# ReleaseRev1.net
KiCad netlist of a schematic drawn in EAGLE
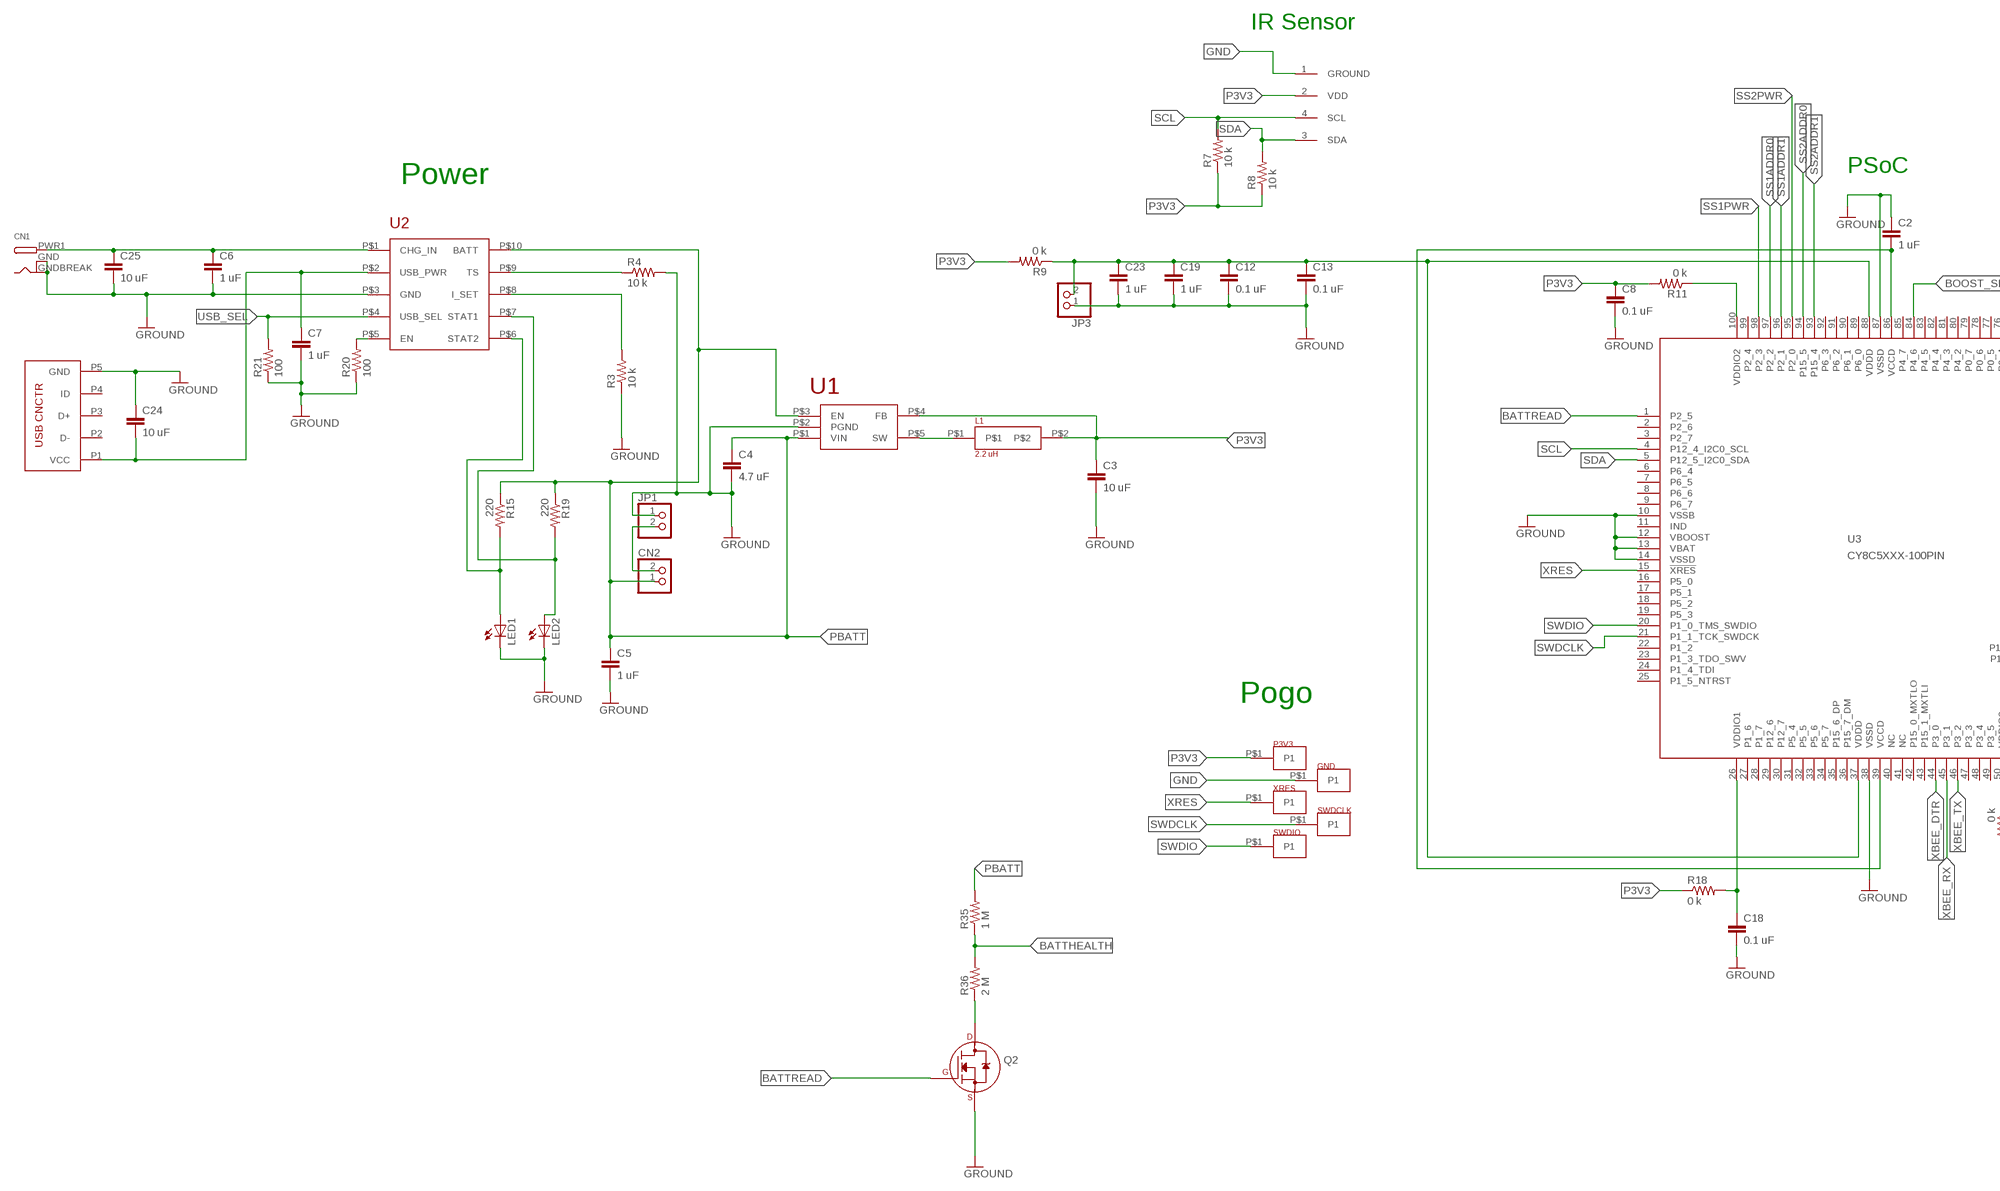
[diagram p0: schematic, sheet 1, part 1 of 2]
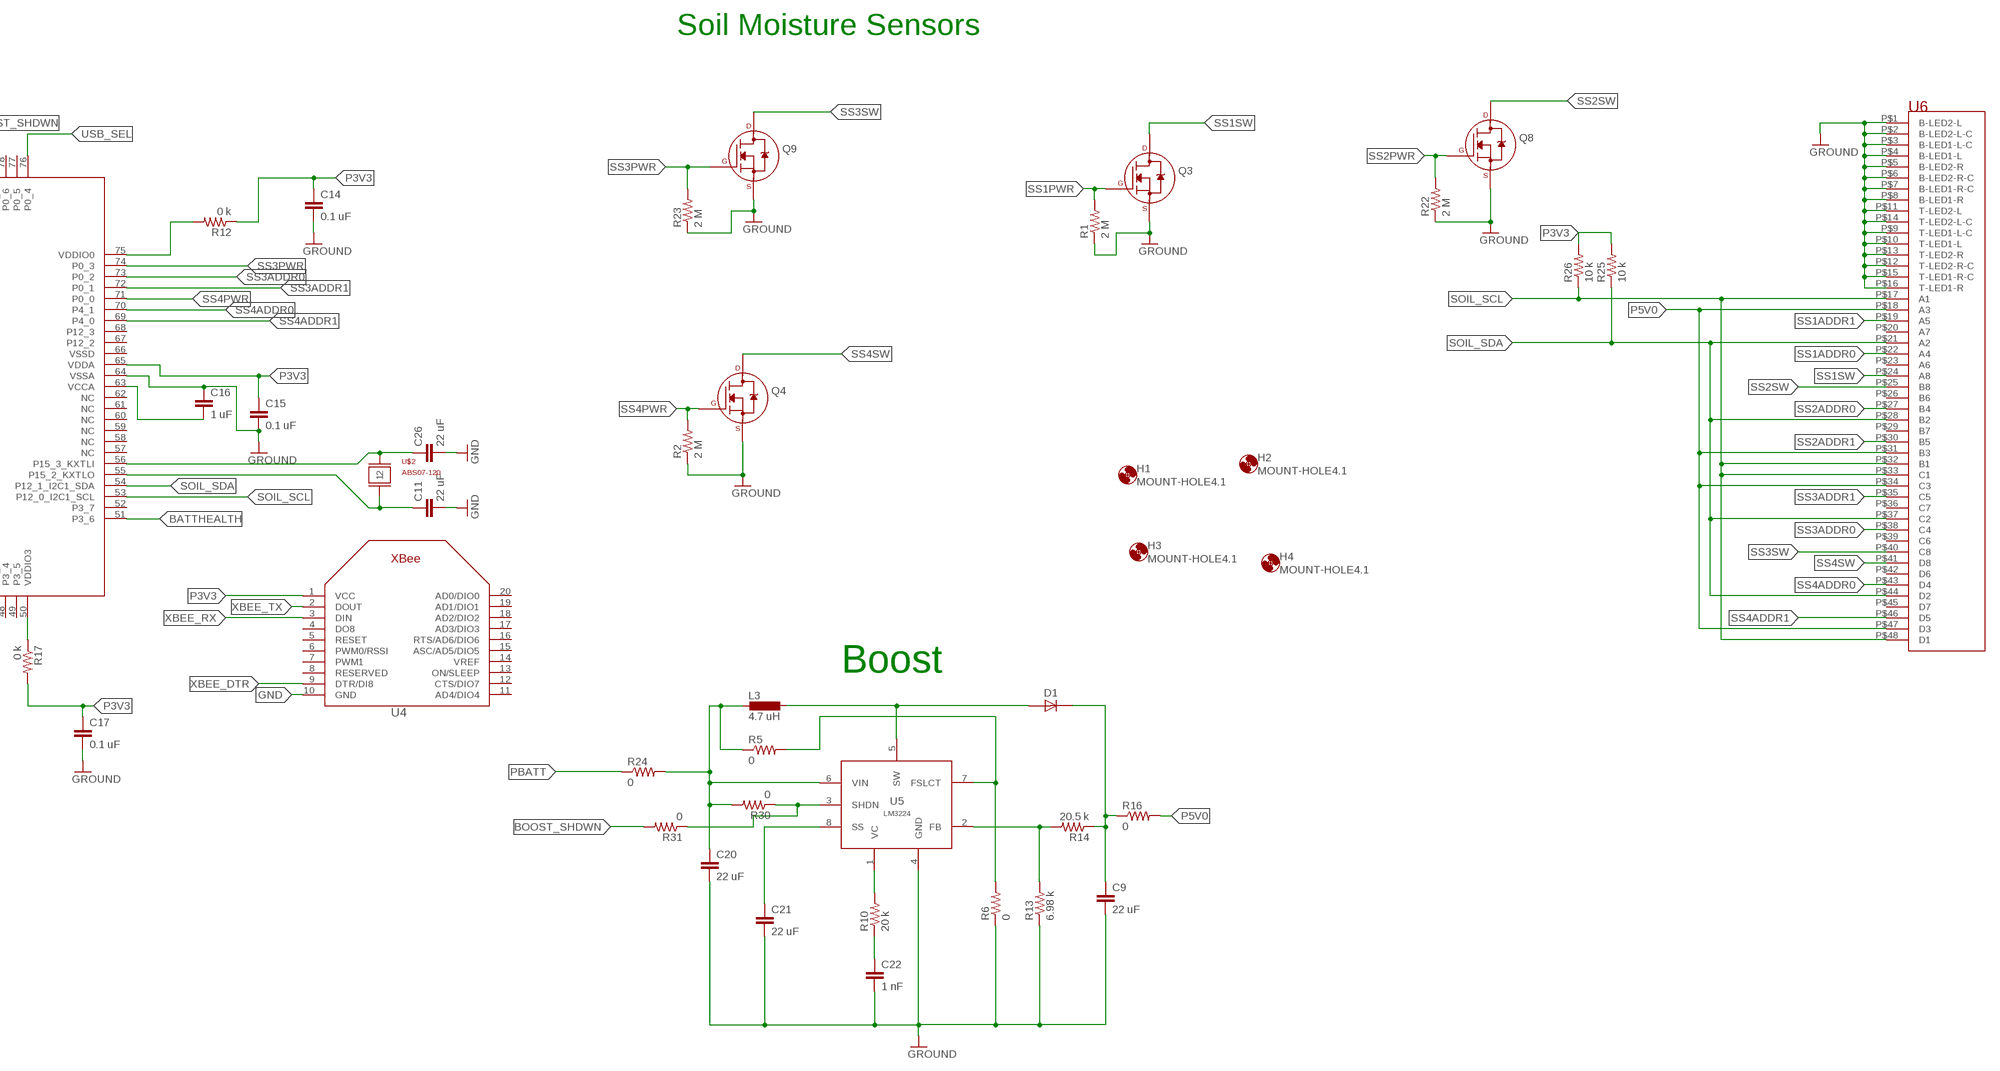
[diagram p1: schematic, sheet 1, part 2 of 2]

(export (version "E")
  (design (tool "Eeschema 10.0.6"))
  (components
    (comp (ref "C2")
      (value "1 uF")
      (footprint "eagle-import:0603")
      (libsource (lib "eagle-import") (part "CAPACITOR0603"))
    )
    (comp (ref "C3")
      (value "10 uF")
      (footprint "eagle-import:0603")
      (libsource (lib "eagle-import") (part "CAPACITOR0603"))
    )
    (comp (ref "C4")
      (value "4.7 uF")
      (footprint "eagle-import:0603")
      (libsource (lib "eagle-import") (part "CAPACITOR0603"))
    )
    (comp (ref "C5")
      (value "1 uF")
      (footprint "eagle-import:0603")
      (libsource (lib "eagle-import") (part "CAPACITOR0603"))
    )
    (comp (ref "C6")
      (value "1 uF")
      (footprint "eagle-import:0603")
      (libsource (lib "eagle-import") (part "CAPACITOR0603"))
    )
    (comp (ref "C7")
      (value "1 uF")
      (footprint "eagle-import:0603")
      (libsource (lib "eagle-import") (part "CAPACITOR0603"))
    )
    (comp (ref "C8")
      (value "0.1 uF")
      (footprint "eagle-import:0603")
      (libsource (lib "eagle-import") (part "CAPACITOR0603"))
    )
    (comp (ref "C9")
      (value "22 uF")
      (footprint "eagle-import:0603")
      (libsource (lib "eagle-import") (part "CAPACITOR0603"))
    )
    (comp (ref "C11")
      (value "22 uF")
      (footprint "eagle-import:0603")
      (libsource (lib "eagle-import") (part "CAPACITOR0603"))
    )
    (comp (ref "C12")
      (value "0.1 uF")
      (footprint "eagle-import:0603")
      (libsource (lib "eagle-import") (part "CAPACITOR0603"))
    )
    (comp (ref "C13")
      (value "0.1 uF")
      (footprint "eagle-import:0603")
      (libsource (lib "eagle-import") (part "CAPACITOR0603"))
    )
    (comp (ref "C14")
      (value "0.1 uF")
      (footprint "eagle-import:0603")
      (libsource (lib "eagle-import") (part "CAPACITOR0603"))
    )
    (comp (ref "C15")
      (value "0.1 uF")
      (footprint "eagle-import:0603")
      (libsource (lib "eagle-import") (part "CAPACITOR0603"))
    )
    (comp (ref "C16")
      (value "1 uF")
      (footprint "eagle-import:0603")
      (libsource (lib "eagle-import") (part "CAPACITOR0603"))
    )
    (comp (ref "C17")
      (value "0.1 uF")
      (footprint "eagle-import:0603")
      (libsource (lib "eagle-import") (part "CAPACITOR0603"))
    )
    (comp (ref "C18")
      (value "0.1 uF")
      (footprint "eagle-import:0603")
      (libsource (lib "eagle-import") (part "CAPACITOR0603"))
    )
    (comp (ref "C19")
      (value "1 uF")
      (footprint "eagle-import:0603")
      (libsource (lib "eagle-import") (part "CAPACITOR0603"))
    )
    (comp (ref "C20")
      (value "22 uF")
      (footprint "eagle-import:0603")
      (libsource (lib "eagle-import") (part "CAPACITOR0603"))
    )
    (comp (ref "C21")
      (value "22 uF")
      (footprint "eagle-import:0603")
      (libsource (lib "eagle-import") (part "CAPACITOR0603"))
    )
    (comp (ref "C22")
      (value "1 nF")
      (footprint "eagle-import:0603")
      (libsource (lib "eagle-import") (part "CAPACITOR0603"))
    )
    (comp (ref "C23")
      (value "1 uF")
      (footprint "eagle-import:0603")
      (libsource (lib "eagle-import") (part "CAPACITOR0603"))
    )
    (comp (ref "C24")
      (value "10 uF")
      (footprint "eagle-import:0603")
      (libsource (lib "eagle-import") (part "CAPACITOR0603"))
    )
    (comp (ref "C25")
      (value "10 uF")
      (footprint "eagle-import:0603")
      (libsource (lib "eagle-import") (part "CAPACITOR0603"))
    )
    (comp (ref "C26")
      (value "22 uF")
      (footprint "eagle-import:0603")
      (libsource (lib "eagle-import") (part "CAPACITOR0603"))
    )
    (comp (ref "CN1")
      (value "DCBARRELSMT")
      (footprint "eagle-import:DCJACK_2MM_SMT")
      (libsource (lib "eagle-import") (part "DCBARRELSMT"))
    )
    (comp (ref "CN2")
      (value "JST_2PIN-SMT-RA")
      (footprint "eagle-import:JST-PH-2-SMT-RA")
      (libsource (lib "eagle-import") (part "JST_2PIN-SMT-RA"))
    )
    (comp (ref "D1")
      (value "DIODE")
      (footprint "eagle-import:0603-LED")
      (libsource (lib "eagle-import") (part "DIODE"))
    )
    (comp (ref "GND")
      (value "POGO-MOUNTING")
      (footprint "eagle-import:POGO-MOUNTING")
      (libsource (lib "eagle-import") (part "POGO-MOUNTING"))
    )
    (comp (ref "H1")
      (value "MOUNT-HOLE4.1")
      (footprint "eagle-import:4,1")
      (libsource (lib "eagle-import") (part "MOUNT-HOLE4.1"))
    )
    (comp (ref "H2")
      (value "MOUNT-HOLE4.1")
      (footprint "eagle-import:4,1")
      (libsource (lib "eagle-import") (part "MOUNT-HOLE4.1"))
    )
    (comp (ref "H3")
      (value "MOUNT-HOLE4.1")
      (footprint "eagle-import:4,1")
      (libsource (lib "eagle-import") (part "MOUNT-HOLE4.1"))
    )
    (comp (ref "H4")
      (value "MOUNT-HOLE4.1")
      (footprint "eagle-import:4,1")
      (libsource (lib "eagle-import") (part "MOUNT-HOLE4.1"))
    )
    (comp (ref "IRSENSOR")
      (value "TO39")
      (footprint "eagle-import:TO39")
      (libsource (lib "eagle-import") (part "TO39"))
    )
    (comp (ref "JP1")
      (value "PINHD-1X2")
      (footprint "eagle-import:1X02")
      (libsource (lib "eagle-import") (part "PINHD-1X2"))
    )
    (comp (ref "JP3")
      (value "PINHD-1X2")
      (footprint "eagle-import:1X02")
      (libsource (lib "eagle-import") (part "PINHD-1X2"))
    )
    (comp (ref "L1")
      (value "LPO3310")
      (footprint "eagle-import:LPO3310")
      (libsource (lib "eagle-import") (part "LPO3310"))
    )
    (comp (ref "L3")
      (value "4.7 uH")
      (footprint "eagle-import:DO3316P")
      (libsource (lib "eagle-import") (part "DO3316P"))
    )
    (comp (ref "LED1")
      (value "LEDCHIP-LED0603")
      (footprint "eagle-import:CHIP-LED0603")
      (libsource (lib "eagle-import") (part "LEDCHIP-LED0603"))
    )
    (comp (ref "LED2")
      (value "LEDCHIP-LED0603")
      (footprint "eagle-import:CHIP-LED0603")
      (libsource (lib "eagle-import") (part "LEDCHIP-LED0603"))
    )
    (comp (ref "P3V3")
      (value "POGO-MOUNTING")
      (footprint "eagle-import:POGO-MOUNTING")
      (libsource (lib "eagle-import") (part "POGO-MOUNTING"))
    )
    (comp (ref "Q2")
      (value "2N7000_SOT23")
      (footprint "eagle-import:SOT-23")
      (libsource (lib "eagle-import") (part "2N700_SOT230"))
    )
    (comp (ref "Q3")
      (value "2N7000_SOT23")
      (footprint "eagle-import:SOT-23")
      (libsource (lib "eagle-import") (part "2N700_SOT230"))
    )
    (comp (ref "Q4")
      (value "2N7000_SOT23")
      (footprint "eagle-import:SOT-23")
      (libsource (lib "eagle-import") (part "2N700_SOT230"))
    )
    (comp (ref "Q8")
      (value "2N7000_SOT23")
      (footprint "eagle-import:SOT-23")
      (libsource (lib "eagle-import") (part "2N700_SOT230"))
    )
    (comp (ref "Q9")
      (value "2N7000_SOT23")
      (footprint "eagle-import:SOT-23")
      (libsource (lib "eagle-import") (part "2N700_SOT230"))
    )
    (comp (ref "R1")
      (value "2 M")
      (footprint "eagle-import:0603")
      (libsource (lib "eagle-import") (part "RESISTOR0603"))
    )
    (comp (ref "R2")
      (value "2 M")
      (footprint "eagle-import:0603")
      (libsource (lib "eagle-import") (part "RESISTOR0603"))
    )
    (comp (ref "R3")
      (value "10 k")
      (footprint "eagle-import:0603")
      (libsource (lib "eagle-import") (part "RESISTOR0603"))
    )
    (comp (ref "R4")
      (value "10 k")
      (footprint "eagle-import:0603")
      (libsource (lib "eagle-import") (part "RESISTOR0603"))
    )
    (comp (ref "R5")
      (value "0")
      (footprint "eagle-import:0603")
      (libsource (lib "eagle-import") (part "RESISTOR0603"))
    )
    (comp (ref "R6")
      (value "0")
      (footprint "eagle-import:0603")
      (libsource (lib "eagle-import") (part "RESISTOR0603"))
    )
    (comp (ref "R7")
      (value "10 k")
      (footprint "eagle-import:0603")
      (libsource (lib "eagle-import") (part "RESISTOR0603"))
    )
    (comp (ref "R8")
      (value "10 k")
      (footprint "eagle-import:0603")
      (libsource (lib "eagle-import") (part "RESISTOR0603"))
    )
    (comp (ref "R9")
      (value "0 k")
      (footprint "eagle-import:0603")
      (libsource (lib "eagle-import") (part "RESISTOR0603"))
    )
    (comp (ref "R10")
      (value "20 k")
      (footprint "eagle-import:0603")
      (libsource (lib "eagle-import") (part "RESISTOR0603"))
    )
    (comp (ref "R11")
      (value "0 k")
      (footprint "eagle-import:0603")
      (libsource (lib "eagle-import") (part "RESISTOR0603"))
    )
    (comp (ref "R12")
      (value "0 k")
      (footprint "eagle-import:0603")
      (libsource (lib "eagle-import") (part "RESISTOR0603"))
    )
    (comp (ref "R13")
      (value "6.98 k")
      (footprint "eagle-import:0603")
      (libsource (lib "eagle-import") (part "RESISTOR0603"))
    )
    (comp (ref "R14")
      (value "20.5 k")
      (footprint "eagle-import:0603")
      (libsource (lib "eagle-import") (part "RESISTOR0603"))
    )
    (comp (ref "R15")
      (value "220")
      (footprint "eagle-import:0603")
      (libsource (lib "eagle-import") (part "RESISTOR0603"))
    )
    (comp (ref "R16")
      (value "0")
      (footprint "eagle-import:R2010")
      (libsource (lib "eagle-import") (part "R-US_R2010"))
    )
    (comp (ref "R17")
      (value "0 k")
      (footprint "eagle-import:0603")
      (libsource (lib "eagle-import") (part "RESISTOR0603"))
    )
    (comp (ref "R18")
      (value "0 k")
      (footprint "eagle-import:0603")
      (libsource (lib "eagle-import") (part "RESISTOR0603"))
    )
    (comp (ref "R19")
      (value "220")
      (footprint "eagle-import:0603")
      (libsource (lib "eagle-import") (part "RESISTOR0603"))
    )
    (comp (ref "R20")
      (value "100")
      (footprint "eagle-import:0603")
      (libsource (lib "eagle-import") (part "RESISTOR0603"))
    )
    (comp (ref "R21")
      (value "100")
      (footprint "eagle-import:0603")
      (libsource (lib "eagle-import") (part "RESISTOR0603"))
    )
    (comp (ref "R22")
      (value "2 M")
      (footprint "eagle-import:0603")
      (libsource (lib "eagle-import") (part "RESISTOR0603"))
    )
    (comp (ref "R23")
      (value "2 M")
      (footprint "eagle-import:0603")
      (libsource (lib "eagle-import") (part "RESISTOR0603"))
    )
    (comp (ref "R24")
      (value "0")
      (footprint "eagle-import:R2010")
      (libsource (lib "eagle-import") (part "R-US_R2010"))
    )
    (comp (ref "R25")
      (value "10 k")
      (footprint "eagle-import:0603")
      (libsource (lib "eagle-import") (part "RESISTOR0603"))
    )
    (comp (ref "R26")
      (value "10 k")
      (footprint "eagle-import:0603")
      (libsource (lib "eagle-import") (part "RESISTOR0603"))
    )
    (comp (ref "R30")
      (value "0")
      (footprint "eagle-import:0603")
      (libsource (lib "eagle-import") (part "RESISTOR0603"))
    )
    (comp (ref "R31")
      (value "0")
      (footprint "eagle-import:0603")
      (libsource (lib "eagle-import") (part "RESISTOR0603"))
    )
    (comp (ref "R35")
      (value "1 M")
      (footprint "eagle-import:0603")
      (libsource (lib "eagle-import") (part "RESISTOR0603"))
    )
    (comp (ref "R36")
      (value "2 M")
      (footprint "eagle-import:0603")
      (libsource (lib "eagle-import") (part "RESISTOR0603"))
    )
    (comp (ref "SWDCLK")
      (value "POGO-MOUNTING")
      (footprint "eagle-import:POGO-MOUNTING")
      (libsource (lib "eagle-import") (part "POGO-MOUNTING"))
    )
    (comp (ref "SWDIO")
      (value "POGO-MOUNTING")
      (footprint "eagle-import:POGO-MOUNTING")
      (libsource (lib "eagle-import") (part "POGO-MOUNTING"))
    )
    (comp (ref "U$1")
      (value "FCI10118192-0001LF")
      (footprint "eagle-import:FCI10118192-0001LF")
      (libsource (lib "eagle-import") (part "FCI10118192-0001LF"))
    )
    (comp (ref "U$2")
      (value "ABS07-120")
      (footprint "eagle-import:2-SMD")
      (libsource (lib "eagle-import") (part "ABS07-120"))
    )
    (comp (ref "U1")
      (value "LM3671-407564")
      (footprint "eagle-import:LM3671-407564")
      (libsource (lib "eagle-import") (part "LM3671-407564"))
    )
    (comp (ref "U2")
      (value "LM3658")
      (footprint "eagle-import:LM3658")
      (libsource (lib "eagle-import") (part "LM3658"))
    )
    (comp (ref "U3")
      (value "CY8C5XXX-100PIN")
      (footprint "eagle-import:TQFP-14X14-100")
      (fields (field (name "MPN") "CY8C5588AXI-060"))
      (libsource (lib "eagle-import") (part "CY8C5XXX-100PIN"))
    )
    (comp (ref "U4")
      (value "XBEE")
      (footprint "eagle-import:XBEE")
      (libsource (lib "eagle-import") (part "XBEE"))
    )
    (comp (ref "U5")
      (value "LM3224")
      (footprint "eagle-import:MSOP-8")
      (libsource (lib "eagle-import") (part "LM3224"))
    )
    (comp (ref "U6")
      (value "RJSAE-5380-04")
      (footprint "eagle-import:RJSAE-5380-04")
      (libsource (lib "eagle-import") (part "RJSAE-5380-04"))
    )
    (comp (ref "XRES")
      (value "POGO-MOUNTING")
      (footprint "eagle-import:POGO-MOUNTING")
      (libsource (lib "eagle-import") (part "POGO-MOUNTING"))
    )
  )
  (nets
    (net (code "1") (name "BATTHEALTH") (class "Default")
      (node (ref "R35") (pin "1") (pinfunction "1_1") (pintype "passive"))
      (node (ref "R36") (pin "2") (pinfunction "2_2") (pintype "passive"))
      (node (ref "U3") (pin "51") (pinfunction "P3_6_51") (pintype "passive"))
    )
    (net (code "2") (name "BATTREAD") (class "Default")
      (node (ref "Q2") (pin "1") (pinfunction "G_1") (pintype "tri_state"))
      (node (ref "U3") (pin "1") (pinfunction "P2_5_1") (pintype "passive"))
    )
    (net (code "3") (name "BOOST_SHDWN") (class "Default")
      (node (ref "R31") (pin "2") (pinfunction "2_2") (pintype "passive"))
      (node (ref "U3") (pin "84") (pinfunction "P4_6_84") (pintype "passive"))
    )
    (net (code "4") (name "GND") (class "Default")
      (node (ref "C11") (pin "2") (pinfunction "2_2") (pintype "passive"))
      (node (ref "C12") (pin "2") (pinfunction "2_2") (pintype "passive"))
      (node (ref "C13") (pin "2") (pinfunction "2_2") (pintype "passive"))
      (node (ref "C14") (pin "2") (pinfunction "2_2") (pintype "passive"))
      (node (ref "C15") (pin "2") (pinfunction "2_2") (pintype "passive"))
      (node (ref "C16") (pin "1") (pinfunction "1_1") (pintype "passive"))
      (node (ref "C17") (pin "2") (pinfunction "2_2") (pintype "passive"))
      (node (ref "C18") (pin "2") (pinfunction "2_2") (pintype "passive"))
      (node (ref "C19") (pin "2") (pinfunction "2_2") (pintype "passive"))
      (node (ref "C2") (pin "1") (pinfunction "1_1") (pintype "passive"))
      (node (ref "C20") (pin "2") (pinfunction "2_2") (pintype "passive"))
      (node (ref "C21") (pin "2") (pinfunction "2_2") (pintype "passive"))
      (node (ref "C22") (pin "2") (pinfunction "2_2") (pintype "passive"))
      (node (ref "C23") (pin "2") (pinfunction "2_2") (pintype "passive"))
      (node (ref "C24") (pin "1") (pinfunction "1_1") (pintype "passive"))
      (node (ref "C25") (pin "2") (pinfunction "2_2") (pintype "passive"))
      (node (ref "C26") (pin "2") (pinfunction "2_2") (pintype "passive"))
      (node (ref "C3") (pin "2") (pinfunction "2_2") (pintype "passive"))
      (node (ref "C4") (pin "2") (pinfunction "2_2") (pintype "passive"))
      (node (ref "C5") (pin "2") (pinfunction "2_2") (pintype "passive"))
      (node (ref "C6") (pin "2") (pinfunction "2_2") (pintype "passive"))
      (node (ref "C7") (pin "2") (pinfunction "2_2") (pintype "passive"))
      (node (ref "C8") (pin "2") (pinfunction "2_2") (pintype "passive"))
      (node (ref "C9") (pin "2") (pinfunction "2_2") (pintype "passive"))
      (node (ref "CN1") (pin "GND") (pinfunction "GNDBREAK_GND") (pintype "power_in"))
      (node (ref "CN1") (pin "GNDBREAK") (pinfunction "GND_GNDBREAK") (pintype "power_in"))
      (node (ref "GND") (pin "P$1") (pinfunction "P1_P$1") (pintype "bidirectional"))
      (node (ref "IRSENSOR") (pin "1") (pinfunction "GROUND_1") (pintype "bidirectional"))
      (node (ref "JP1") (pin "1") (pinfunction "1_1") (pintype "passive"))
      (node (ref "JP3") (pin "1") (pinfunction "1_1") (pintype "passive"))
      (node (ref "LED1") (pin "C") (pinfunction "C_C") (pintype "passive"))
      (node (ref "LED2") (pin "C") (pinfunction "C_C") (pintype "passive"))
      (node (ref "Q2") (pin "2") (pinfunction "S_2") (pintype "bidirectional"))
      (node (ref "Q3") (pin "2") (pinfunction "S_2") (pintype "bidirectional"))
      (node (ref "Q4") (pin "2") (pinfunction "S_2") (pintype "bidirectional"))
      (node (ref "Q8") (pin "2") (pinfunction "S_2") (pintype "bidirectional"))
      (node (ref "Q9") (pin "2") (pinfunction "S_2") (pintype "bidirectional"))
      (node (ref "R1") (pin "1") (pinfunction "1_1") (pintype "passive"))
      (node (ref "R13") (pin "1") (pinfunction "1_1") (pintype "passive"))
      (node (ref "R2") (pin "1") (pinfunction "1_1") (pintype "passive"))
      (node (ref "R20") (pin "1") (pinfunction "1_1") (pintype "passive"))
      (node (ref "R21") (pin "1") (pinfunction "1_1") (pintype "passive"))
      (node (ref "R22") (pin "1") (pinfunction "1_1") (pintype "passive"))
      (node (ref "R23") (pin "1") (pinfunction "1_1") (pintype "passive"))
      (node (ref "R3") (pin "1") (pinfunction "1_1") (pintype "passive"))
      (node (ref "R4") (pin "2") (pinfunction "2_2") (pintype "passive"))
      (node (ref "R6") (pin "1") (pinfunction "1_1") (pintype "passive"))
      (node (ref "U$1") (pin "P5") (pinfunction "GND_P5") (pintype "power_in"))
      (node (ref "U1") (pin "P$2") (pinfunction "PGND_P$2") (pintype "passive"))
      (node (ref "U2") (pin "P$3") (pinfunction "GND_P$3") (pintype "power_in"))
      (node (ref "U3") (pin "10") (pinfunction "VSSB_10") (pintype "passive"))
      (node (ref "U3") (pin "12") (pinfunction "VBOOST_12") (pintype "passive"))
      (node (ref "U3") (pin "13") (pinfunction "VBAT_13") (pintype "passive"))
      (node (ref "U3") (pin "14") (pinfunction "VSSD_14") (pintype "passive"))
      (node (ref "U3") (pin "38") (pinfunction "VSSD_38") (pintype "passive"))
      (node (ref "U3") (pin "64") (pinfunction "VSSA_64") (pintype "passive"))
      (node (ref "U3") (pin "87") (pinfunction "VSSD_87") (pintype "passive"))
      (node (ref "U4") (pin "10") (pinfunction "GND_10") (pintype "power_in"))
      (node (ref "U5") (pin "4") (pinfunction "GND_4") (pintype "bidirectional"))
      (node (ref "U6") (pin "P$1") (pinfunction "B-LED2-L_P$1") (pintype "bidirectional"))
      (node (ref "U6") (pin "P$10") (pinfunction "T-LED1-L_P$10") (pintype "bidirectional"))
      (node (ref "U6") (pin "P$11") (pinfunction "T-LED2-L_P$11") (pintype "bidirectional"))
      (node (ref "U6") (pin "P$12") (pinfunction "T-LED2-R-C_P$12") (pintype "bidirectional"))
      (node (ref "U6") (pin "P$13") (pinfunction "T-LED2-R_P$13") (pintype "bidirectional"))
      (node (ref "U6") (pin "P$14") (pinfunction "T-LED2-L-C_P$14") (pintype "bidirectional"))
      (node (ref "U6") (pin "P$15") (pinfunction "T-LED1-R-C_P$15") (pintype "bidirectional"))
      (node (ref "U6") (pin "P$16") (pinfunction "T-LED1-R_P$16") (pintype "bidirectional"))
      (node (ref "U6") (pin "P$2") (pinfunction "B-LED2-L-C_P$2") (pintype "bidirectional"))
      (node (ref "U6") (pin "P$3") (pinfunction "B-LED1-L-C_P$3") (pintype "bidirectional"))
      (node (ref "U6") (pin "P$4") (pinfunction "B-LED1-L_P$4") (pintype "bidirectional"))
      (node (ref "U6") (pin "P$5") (pinfunction "B-LED2-R_P$5") (pintype "bidirectional"))
      (node (ref "U6") (pin "P$6") (pinfunction "B-LED2-R-C_P$6") (pintype "bidirectional"))
      (node (ref "U6") (pin "P$7") (pinfunction "B-LED1-R-C_P$7") (pintype "bidirectional"))
      (node (ref "U6") (pin "P$8") (pinfunction "B-LED1-R_P$8") (pintype "bidirectional"))
      (node (ref "U6") (pin "P$9") (pinfunction "T-LED1-L-C_P$9") (pintype "bidirectional"))
    )
    (net (code "5") (name "Net-(C2-Pad2)") (class "Default")
      (node (ref "C2") (pin "2") (pinfunction "2_2") (pintype "passive"))
      (node (ref "U3") (pin "39") (pinfunction "VCCD_39") (pintype "passive"))
      (node (ref "U3") (pin "86") (pinfunction "VCCD_86") (pintype "passive"))
    )
    (net (code "6") (name "Net-(C9-Pad1)") (class "Default")
      (node (ref "C9") (pin "1") (pinfunction "1_1") (pintype "passive"))
      (node (ref "D1") (pin "C") (pinfunction "C_C") (pintype "passive"))
      (node (ref "R14") (pin "1") (pinfunction "1_1") (pintype "passive"))
      (node (ref "R16") (pin "1") (pinfunction "1_1") (pintype "passive"))
    )
    (net (code "7") (name "Net-(C12-Pad1)") (class "Default")
      (node (ref "C12") (pin "1") (pinfunction "1_1") (pintype "passive"))
      (node (ref "C13") (pin "1") (pinfunction "1_1") (pintype "passive"))
      (node (ref "C19") (pin "1") (pinfunction "1_1") (pintype "passive"))
      (node (ref "C23") (pin "1") (pinfunction "1_1") (pintype "passive"))
      (node (ref "JP3") (pin "2") (pinfunction "2_2") (pintype "passive"))
      (node (ref "R9") (pin "1") (pinfunction "1_1") (pintype "passive"))
      (node (ref "U3") (pin "37") (pinfunction "VDDD_37") (pintype "passive"))
      (node (ref "U3") (pin "88") (pinfunction "VDDD_88") (pintype "passive"))
    )
    (net (code "8") (name "Net-(C22-Pad1)") (class "Default")
      (node (ref "C22") (pin "1") (pinfunction "1_1") (pintype "passive"))
      (node (ref "R10") (pin "1") (pinfunction "1_1") (pintype "passive"))
    )
    (net (code "9") (name "Net-(CN1-PWR)") (class "Default")
      (node (ref "C25") (pin "1") (pinfunction "1_1") (pintype "passive"))
      (node (ref "C6") (pin "1") (pinfunction "1_1") (pintype "passive"))
      (node (ref "CN1") (pin "PWR1") (pinfunction "PWR_PWR1") (pintype "power_in"))
      (node (ref "U2") (pin "P$1") (pinfunction "CHG_IN_P$1") (pintype "power_in"))
    )
    (net (code "10") (name "Net-(CN2-1)") (class "Default")
      (node (ref "CN2") (pin "2") (pinfunction "1_2") (pintype "passive"))
      (node (ref "JP1") (pin "2") (pinfunction "2_2") (pintype "passive"))
    )
    (net (code "11") (name "Net-(Q2-D)") (class "Default")
      (node (ref "Q2") (pin "3") (pinfunction "D_3") (pintype "bidirectional"))
      (node (ref "R36") (pin "1") (pinfunction "1_1") (pintype "passive"))
    )
    (net (code "12") (name "Net-(U$1-VCC)") (class "Default")
      (node (ref "C24") (pin "2") (pinfunction "2_2") (pintype "passive"))
      (node (ref "C7") (pin "1") (pinfunction "1_1") (pintype "passive"))
      (node (ref "U$1") (pin "P1") (pinfunction "VCC_P1") (pintype "power_in"))
      (node (ref "U2") (pin "P$2") (pinfunction "USB_PWR_P$2") (pintype "power_in"))
    )
    (net (code "13") (name "Net-(U1-SW)") (class "Default")
      (node (ref "L1") (pin "P$1") (pinfunction "P$1_P$1") (pintype "passive"))
      (node (ref "U1") (pin "P$5") (pinfunction "SW_P$5") (pintype "bidirectional"))
    )
    (net (code "14") (name "Net-(U2-EN)") (class "Default")
      (node (ref "R20") (pin "2") (pinfunction "2_2") (pintype "passive"))
      (node (ref "U2") (pin "P$5") (pinfunction "EN_P$5") (pintype "input"))
    )
    (net (code "15") (name "Net-(U2-I_SET)") (class "Default")
      (node (ref "R3") (pin "2") (pinfunction "2_2") (pintype "passive"))
      (node (ref "U2") (pin "P$8") (pinfunction "I_SET_P$8") (pintype "bidirectional"))
    )
    (net (code "16") (name "Net-(U2-STAT1)") (class "Default")
      (node (ref "LED2") (pin "A") (pinfunction "A_A") (pintype "passive"))
      (node (ref "R19") (pin "2") (pinfunction "2_2") (pintype "passive"))
      (node (ref "U2") (pin "P$7") (pinfunction "STAT1_P$7") (pintype "output"))
    )
    (net (code "17") (name "Net-(U2-STAT2)") (class "Default")
      (node (ref "LED1") (pin "A") (pinfunction "A_A") (pintype "passive"))
      (node (ref "R15") (pin "2") (pinfunction "2_2") (pintype "passive"))
      (node (ref "U2") (pin "P$6") (pinfunction "STAT2_P$6") (pintype "output"))
    )
    (net (code "18") (name "Net-(U2-TS)") (class "Default")
      (node (ref "R4") (pin "1") (pinfunction "1_1") (pintype "passive"))
      (node (ref "U2") (pin "P$9") (pinfunction "TS_P$9") (pintype "bidirectional"))
    )
    (net (code "19") (name "Net-(U3-P15_2_KXTLO)") (class "Default")
      (node (ref "C11") (pin "1") (pinfunction "1_1") (pintype "passive"))
      (node (ref "U$2") (pin "2") (pinfunction "2_2") (pintype "bidirectional"))
      (node (ref "U3") (pin "55") (pinfunction "P15_2_KXTLO_55") (pintype "passive"))
    )
    (net (code "20") (name "Net-(U3-P15_3_KXTLI)") (class "Default")
      (node (ref "C26") (pin "1") (pinfunction "1_1") (pintype "passive"))
      (node (ref "U$2") (pin "1") (pinfunction "1_1") (pintype "bidirectional"))
      (node (ref "U3") (pin "56") (pinfunction "P15_3_KXTLI_56") (pintype "passive"))
    )
    (net (code "21") (name "Net-(U3-VCCA)") (class "Default")
      (node (ref "C16") (pin "2") (pinfunction "2_2") (pintype "passive"))
      (node (ref "U3") (pin "63") (pinfunction "VCCA_63") (pintype "passive"))
    )
    (net (code "22") (name "Net-(U3-VDDIO0)") (class "Default")
      (node (ref "R12") (pin "2") (pinfunction "2_2") (pintype "passive"))
      (node (ref "U3") (pin "75") (pinfunction "VDDIO0_75") (pintype "passive"))
    )
    (net (code "23") (name "Net-(U3-VDDIO1)") (class "Default")
      (node (ref "C18") (pin "1") (pinfunction "1_1") (pintype "passive"))
      (node (ref "R18") (pin "2") (pinfunction "2_2") (pintype "passive"))
      (node (ref "U3") (pin "26") (pinfunction "VDDIO1_26") (pintype "passive"))
    )
    (net (code "24") (name "Net-(U3-VDDIO2)") (class "Default")
      (node (ref "R11") (pin "1") (pinfunction "1_1") (pintype "passive"))
      (node (ref "U3") (pin "100") (pinfunction "VDDIO2_100") (pintype "passive"))
    )
    (net (code "25") (name "Net-(U3-VDDIO3)") (class "Default")
      (node (ref "R17") (pin "1") (pinfunction "1_1") (pintype "passive"))
      (node (ref "U3") (pin "50") (pinfunction "VDDIO3_50") (pintype "passive"))
    )
    (net (code "26") (name "Net-(U5-FB)") (class "Default")
      (node (ref "R13") (pin "2") (pinfunction "2_2") (pintype "passive"))
      (node (ref "R14") (pin "2") (pinfunction "2_2") (pintype "passive"))
      (node (ref "U5") (pin "2") (pinfunction "FB_2") (pintype "bidirectional"))
    )
    (net (code "27") (name "Net-(U5-FSLCT)") (class "Default")
      (node (ref "R5") (pin "2") (pinfunction "2_2") (pintype "passive"))
      (node (ref "R6") (pin "2") (pinfunction "2_2") (pintype "passive"))
      (node (ref "U5") (pin "7") (pinfunction "FSLCT_7") (pintype "bidirectional"))
    )
    (net (code "28") (name "Net-(U5-SHDN)") (class "Default")
      (node (ref "R30") (pin "1") (pinfunction "1_1") (pintype "passive"))
      (node (ref "R31") (pin "1") (pinfunction "1_1") (pintype "passive"))
      (node (ref "U5") (pin "3") (pinfunction "SHDN_3") (pintype "bidirectional"))
    )
    (net (code "29") (name "Net-(U5-SS)") (class "Default")
      (node (ref "C21") (pin "1") (pinfunction "1_1") (pintype "passive"))
      (node (ref "U5") (pin "8") (pinfunction "SS_8") (pintype "bidirectional"))
    )
    (net (code "30") (name "Net-(U5-SW)") (class "Default")
      (node (ref "D1") (pin "A") (pinfunction "A_A") (pintype "passive"))
      (node (ref "L3") (pin "2") (pinfunction "2_2") (pintype "passive"))
      (node (ref "U5") (pin "5") (pinfunction "SW_5") (pintype "bidirectional"))
    )
    (net (code "31") (name "Net-(U5-VC)") (class "Default")
      (node (ref "R10") (pin "2") (pinfunction "2_2") (pintype "passive"))
      (node (ref "U5") (pin "1") (pinfunction "VC_1") (pintype "bidirectional"))
    )
    (net (code "32") (name "Net-(U5-VIN)") (class "Default")
      (node (ref "C20") (pin "1") (pinfunction "1_1") (pintype "passive"))
      (node (ref "L3") (pin "1") (pinfunction "1_1") (pintype "passive"))
      (node (ref "R24") (pin "2") (pinfunction "2_2") (pintype "passive"))
      (node (ref "R30") (pin "2") (pinfunction "2_2") (pintype "passive"))
      (node (ref "R5") (pin "1") (pinfunction "1_1") (pintype "passive"))
      (node (ref "U5") (pin "6") (pinfunction "VIN_6") (pintype "bidirectional"))
    )
    (net (code "33") (name "P3V3") (class "Default")
      (node (ref "C14") (pin "1") (pinfunction "1_1") (pintype "passive"))
      (node (ref "C15") (pin "1") (pinfunction "1_1") (pintype "passive"))
      (node (ref "C17") (pin "1") (pinfunction "1_1") (pintype "passive"))
      (node (ref "C3") (pin "1") (pinfunction "1_1") (pintype "passive"))
      (node (ref "C8") (pin "1") (pinfunction "1_1") (pintype "passive"))
      (node (ref "IRSENSOR") (pin "2") (pinfunction "VDD_2") (pintype "bidirectional"))
      (node (ref "L1") (pin "P$2") (pinfunction "P$2_P$2") (pintype "tri_state"))
      (node (ref "P3V3") (pin "P$1") (pinfunction "P1_P$1") (pintype "bidirectional"))
      (node (ref "R11") (pin "2") (pinfunction "2_2") (pintype "passive"))
      (node (ref "R12") (pin "1") (pinfunction "1_1") (pintype "passive"))
      (node (ref "R17") (pin "2") (pinfunction "2_2") (pintype "passive"))
      (node (ref "R18") (pin "1") (pinfunction "1_1") (pintype "passive"))
      (node (ref "R25") (pin "2") (pinfunction "2_2") (pintype "passive"))
      (node (ref "R26") (pin "2") (pinfunction "2_2") (pintype "passive"))
      (node (ref "R7") (pin "1") (pinfunction "1_1") (pintype "passive"))
      (node (ref "R8") (pin "1") (pinfunction "1_1") (pintype "passive"))
      (node (ref "R9") (pin "2") (pinfunction "2_2") (pintype "passive"))
      (node (ref "U1") (pin "P$4") (pinfunction "FB_P$4") (pintype "bidirectional"))
      (node (ref "U3") (pin "65") (pinfunction "VDDA_65") (pintype "passive"))
      (node (ref "U4") (pin "1") (pinfunction "VCC_1") (pintype "power_in"))
    )
    (net (code "34") (name "P5V0") (class "Default")
      (node (ref "R16") (pin "2") (pinfunction "2_2") (pintype "passive"))
      (node (ref "U6") (pin "P$18") (pinfunction "A3_P$18") (pintype "bidirectional"))
      (node (ref "U6") (pin "P$31") (pinfunction "B3_P$31") (pintype "bidirectional"))
      (node (ref "U6") (pin "P$34") (pinfunction "C3_P$34") (pintype "bidirectional"))
      (node (ref "U6") (pin "P$47") (pinfunction "D3_P$47") (pintype "bidirectional"))
    )
    (net (code "35") (name "PBATT") (class "Default")
      (node (ref "C4") (pin "1") (pinfunction "1_1") (pintype "passive"))
      (node (ref "C5") (pin "1") (pinfunction "1_1") (pintype "passive"))
      (node (ref "CN2") (pin "1") (pinfunction "2_1") (pintype "passive"))
      (node (ref "R15") (pin "1") (pinfunction "1_1") (pintype "passive"))
      (node (ref "R19") (pin "1") (pinfunction "1_1") (pintype "passive"))
      (node (ref "R24") (pin "1") (pinfunction "1_1") (pintype "passive"))
      (node (ref "R35") (pin "2") (pinfunction "2_2") (pintype "passive"))
      (node (ref "U1") (pin "P$1") (pinfunction "VIN_P$1") (pintype "power_in"))
      (node (ref "U1") (pin "P$3") (pinfunction "EN_P$3") (pintype "bidirectional"))
      (node (ref "U2") (pin "P$10") (pinfunction "BATT_P$10") (pintype "power_in"))
    )
    (net (code "36") (name "SCL") (class "Default")
      (node (ref "IRSENSOR") (pin "4") (pinfunction "SCL_4") (pintype "bidirectional"))
      (node (ref "R7") (pin "2") (pinfunction "2_2") (pintype "passive"))
      (node (ref "U3") (pin "4") (pinfunction "P12_4_I2C0_SCL_4") (pintype "passive"))
    )
    (net (code "37") (name "SDA") (class "Default")
      (node (ref "IRSENSOR") (pin "3") (pinfunction "SDA_3") (pintype "bidirectional"))
      (node (ref "R8") (pin "2") (pinfunction "2_2") (pintype "passive"))
      (node (ref "U3") (pin "5") (pinfunction "P12_5_I2C0_SDA_5") (pintype "passive"))
    )
    (net (code "38") (name "SOIL_SCL") (class "Default")
      (node (ref "R26") (pin "1") (pinfunction "1_1") (pintype "passive"))
      (node (ref "U3") (pin "53") (pinfunction "P12_0_I2C1_SCL_53") (pintype "passive"))
      (node (ref "U6") (pin "P$17") (pinfunction "A1_P$17") (pintype "bidirectional"))
      (node (ref "U6") (pin "P$32") (pinfunction "B1_P$32") (pintype "bidirectional"))
      (node (ref "U6") (pin "P$33") (pinfunction "C1_P$33") (pintype "bidirectional"))
      (node (ref "U6") (pin "P$48") (pinfunction "D1_P$48") (pintype "bidirectional"))
    )
    (net (code "39") (name "SOIL_SDA") (class "Default")
      (node (ref "R25") (pin "1") (pinfunction "1_1") (pintype "passive"))
      (node (ref "U3") (pin "54") (pinfunction "P12_1_I2C1_SDA_54") (pintype "passive"))
      (node (ref "U6") (pin "P$21") (pinfunction "A2_P$21") (pintype "bidirectional"))
      (node (ref "U6") (pin "P$28") (pinfunction "B2_P$28") (pintype "bidirectional"))
      (node (ref "U6") (pin "P$37") (pinfunction "C2_P$37") (pintype "bidirectional"))
      (node (ref "U6") (pin "P$44") (pinfunction "D2_P$44") (pintype "bidirectional"))
    )
    (net (code "40") (name "SS1ADDR0") (class "Default")
      (node (ref "U3") (pin "97") (pinfunction "P2_2_97") (pintype "passive"))
      (node (ref "U6") (pin "P$22") (pinfunction "A4_P$22") (pintype "bidirectional"))
    )
    (net (code "41") (name "SS1ADDR1") (class "Default")
      (node (ref "U3") (pin "96") (pinfunction "P2_1_96") (pintype "passive"))
      (node (ref "U6") (pin "P$19") (pinfunction "A5_P$19") (pintype "bidirectional"))
    )
    (net (code "42") (name "SS1PWR") (class "Default")
      (node (ref "Q3") (pin "1") (pinfunction "G_1") (pintype "tri_state"))
      (node (ref "R1") (pin "2") (pinfunction "2_2") (pintype "passive"))
      (node (ref "U3") (pin "98") (pinfunction "P2_3_98") (pintype "passive"))
    )
    (net (code "43") (name "SS1SW") (class "Default")
      (node (ref "Q3") (pin "3") (pinfunction "D_3") (pintype "bidirectional"))
      (node (ref "U6") (pin "P$24") (pinfunction "A8_P$24") (pintype "bidirectional"))
    )
    (net (code "44") (name "SS2ADDR0") (class "Default")
      (node (ref "U3") (pin "94") (pinfunction "P15_5_94") (pintype "passive"))
      (node (ref "U6") (pin "P$27") (pinfunction "B4_P$27") (pintype "bidirectional"))
    )
    (net (code "45") (name "SS2ADDR1") (class "Default")
      (node (ref "U3") (pin "93") (pinfunction "P15_4_93") (pintype "passive"))
      (node (ref "U6") (pin "P$30") (pinfunction "B5_P$30") (pintype "bidirectional"))
    )
    (net (code "46") (name "SS2PWR") (class "Default")
      (node (ref "Q8") (pin "1") (pinfunction "G_1") (pintype "tri_state"))
      (node (ref "R22") (pin "2") (pinfunction "2_2") (pintype "passive"))
      (node (ref "U3") (pin "95") (pinfunction "P2_0_95") (pintype "passive"))
    )
    (net (code "47") (name "SS2SW") (class "Default")
      (node (ref "Q8") (pin "3") (pinfunction "D_3") (pintype "bidirectional"))
      (node (ref "U6") (pin "P$25") (pinfunction "B8_P$25") (pintype "bidirectional"))
    )
    (net (code "48") (name "SS3ADDR0") (class "Default")
      (node (ref "U3") (pin "73") (pinfunction "P0_2_73") (pintype "passive"))
      (node (ref "U6") (pin "P$38") (pinfunction "C4_P$38") (pintype "bidirectional"))
    )
    (net (code "49") (name "SS3ADDR1") (class "Default")
      (node (ref "U3") (pin "72") (pinfunction "P0_1_72") (pintype "passive"))
      (node (ref "U6") (pin "P$35") (pinfunction "C5_P$35") (pintype "bidirectional"))
    )
    (net (code "50") (name "SS3PWR") (class "Default")
      (node (ref "Q9") (pin "1") (pinfunction "G_1") (pintype "tri_state"))
      (node (ref "R23") (pin "2") (pinfunction "2_2") (pintype "passive"))
      (node (ref "U3") (pin "74") (pinfunction "P0_3_74") (pintype "passive"))
    )
    (net (code "51") (name "SS3SW") (class "Default")
      (node (ref "Q9") (pin "3") (pinfunction "D_3") (pintype "bidirectional"))
      (node (ref "U6") (pin "P$40") (pinfunction "C8_P$40") (pintype "bidirectional"))
    )
    (net (code "52") (name "SS4ADDR0") (class "Default")
      (node (ref "U3") (pin "70") (pinfunction "P4_1_70") (pintype "passive"))
      (node (ref "U6") (pin "P$43") (pinfunction "D4_P$43") (pintype "bidirectional"))
    )
    (net (code "53") (name "SS4ADDR1") (class "Default")
      (node (ref "U3") (pin "69") (pinfunction "P4_0_69") (pintype "passive"))
      (node (ref "U6") (pin "P$46") (pinfunction "D5_P$46") (pintype "bidirectional"))
    )
    (net (code "54") (name "SS4PWR") (class "Default")
      (node (ref "Q4") (pin "1") (pinfunction "G_1") (pintype "tri_state"))
      (node (ref "R2") (pin "2") (pinfunction "2_2") (pintype "passive"))
      (node (ref "U3") (pin "71") (pinfunction "P0_0_71") (pintype "passive"))
    )
    (net (code "55") (name "SS4SW") (class "Default")
      (node (ref "Q4") (pin "3") (pinfunction "D_3") (pintype "bidirectional"))
      (node (ref "U6") (pin "P$41") (pinfunction "D8_P$41") (pintype "bidirectional"))
    )
    (net (code "56") (name "SWDCLK") (class "Default")
      (node (ref "SWDCLK") (pin "P$1") (pinfunction "P1_P$1") (pintype "bidirectional"))
      (node (ref "U3") (pin "21") (pinfunction "P1_1_TCK_SWDCK_21") (pintype "passive"))
    )
    (net (code "57") (name "SWDIO") (class "Default")
      (node (ref "SWDIO") (pin "P$1") (pinfunction "P1_P$1") (pintype "bidirectional"))
      (node (ref "U3") (pin "20") (pinfunction "P1_0_TMS_SWDIO_20") (pintype "passive"))
    )
    (net (code "58") (name "USB_SEL") (class "Default")
      (node (ref "R21") (pin "2") (pinfunction "2_2") (pintype "passive"))
      (node (ref "U2") (pin "P$4") (pinfunction "USB_SEL_P$4") (pintype "input"))
      (node (ref "U3") (pin "76") (pinfunction "P0_4_76") (pintype "passive"))
    )
    (net (code "59") (name "XBEE_DTR") (class "Default")
      (node (ref "U3") (pin "44") (pinfunction "P3_0_44") (pintype "passive"))
      (node (ref "U4") (pin "9") (pinfunction "DTR/DI8_9") (pintype "input"))
    )
    (net (code "60") (name "XBEE_RX") (class "Default")
      (node (ref "U3") (pin "45") (pinfunction "P3_1_45") (pintype "passive"))
      (node (ref "U4") (pin "3") (pinfunction "DIN_3") (pintype "input"))
    )
    (net (code "61") (name "XBEE_TX") (class "Default")
      (node (ref "U3") (pin "46") (pinfunction "P3_2_46") (pintype "passive"))
      (node (ref "U4") (pin "2") (pinfunction "DOUT_2") (pintype "output"))
    )
    (net (code "62") (name "XRES") (class "Default")
      (node (ref "U3") (pin "15") (pinfunction "~{XRES}_15") (pintype "passive"))
      (node (ref "XRES") (pin "P$1") (pinfunction "P1_P$1") (pintype "bidirectional"))
    )
    (net (code "63") (name "unconnected-(U$1-D+-PadP3)") (class "Default")
      (node (ref "U$1") (pin "P3") (pinfunction "D+_P3") (pintype "bidirectional"))
    )
    (net (code "64") (name "unconnected-(U$1-D--PadP2)") (class "Default")
      (node (ref "U$1") (pin "P2") (pinfunction "D-_P2") (pintype "bidirectional"))
    )
    (net (code "65") (name "unconnected-(U$1-ID-PadP4)") (class "Default")
      (node (ref "U$1") (pin "P4") (pinfunction "ID_P4") (pintype "bidirectional"))
    )
    (net (code "66") (name "unconnected-(U3-IND-Pad11)") (class "Default")
      (node (ref "U3") (pin "11") (pinfunction "IND_11") (pintype "passive"))
    )
    (net (code "67") (name "unconnected-(U3-NC-Pad40)") (class "Default")
      (node (ref "U3") (pin "40") (pinfunction "NC_40") (pintype "passive"))
    )
    (net (code "68") (name "unconnected-(U3-NC-Pad41)") (class "Default")
      (node (ref "U3") (pin "41") (pinfunction "NC_41") (pintype "passive"))
    )
    (net (code "69") (name "unconnected-(U3-NC-Pad57)") (class "Default")
      (node (ref "U3") (pin "57") (pinfunction "NC_57") (pintype "passive"))
    )
    (net (code "70") (name "unconnected-(U3-NC-Pad58)") (class "Default")
      (node (ref "U3") (pin "58") (pinfunction "NC_58") (pintype "passive"))
    )
    (net (code "71") (name "unconnected-(U3-NC-Pad59)") (class "Default")
      (node (ref "U3") (pin "59") (pinfunction "NC_59") (pintype "passive"))
    )
    (net (code "72") (name "unconnected-(U3-NC-Pad60)") (class "Default")
      (node (ref "U3") (pin "60") (pinfunction "NC_60") (pintype "passive"))
    )
    (net (code "73") (name "unconnected-(U3-NC-Pad61)") (class "Default")
      (node (ref "U3") (pin "61") (pinfunction "NC_61") (pintype "passive"))
    )
    (net (code "74") (name "unconnected-(U3-NC-Pad62)") (class "Default")
      (node (ref "U3") (pin "62") (pinfunction "NC_62") (pintype "passive"))
    )
    (net (code "75") (name "unconnected-(U3-P0_5-Pad77)") (class "Default")
      (node (ref "U3") (pin "77") (pinfunction "P0_5_77") (pintype "passive"))
    )
    (net (code "76") (name "unconnected-(U3-P0_6-Pad78)") (class "Default")
      (node (ref "U3") (pin "78") (pinfunction "P0_6_78") (pintype "passive"))
    )
    (net (code "77") (name "unconnected-(U3-P0_7-Pad79)") (class "Default")
      (node (ref "U3") (pin "79") (pinfunction "P0_7_79") (pintype "passive"))
    )
    (net (code "78") (name "unconnected-(U3-P1_2-Pad22)") (class "Default")
      (node (ref "U3") (pin "22") (pinfunction "P1_2_22") (pintype "passive"))
    )
    (net (code "79") (name "unconnected-(U3-P1_3_TDO_SWV-Pad23)") (class "Default")
      (node (ref "U3") (pin "23") (pinfunction "P1_3_TDO_SWV_23") (pintype "passive"))
    )
    (net (code "80") (name "unconnected-(U3-P1_4_TDI-Pad24)") (class "Default")
      (node (ref "U3") (pin "24") (pinfunction "P1_4_TDI_24") (pintype "passive"))
    )
    (net (code "81") (name "unconnected-(U3-P1_5_NTRST-Pad25)") (class "Default")
      (node (ref "U3") (pin "25") (pinfunction "P1_5_NTRST_25") (pintype "passive"))
    )
    (net (code "82") (name "unconnected-(U3-P1_6-Pad27)") (class "Default")
      (node (ref "U3") (pin "27") (pinfunction "P1_6_27") (pintype "passive"))
    )
    (net (code "83") (name "unconnected-(U3-P1_7-Pad28)") (class "Default")
      (node (ref "U3") (pin "28") (pinfunction "P1_7_28") (pintype "passive"))
    )
    (net (code "84") (name "unconnected-(U3-P2_4-Pad99)") (class "Default")
      (node (ref "U3") (pin "99") (pinfunction "P2_4_99") (pintype "passive"))
    )
    (net (code "85") (name "unconnected-(U3-P2_6-Pad2)") (class "Default")
      (node (ref "U3") (pin "2") (pinfunction "P2_6_2") (pintype "passive"))
    )
    (net (code "86") (name "unconnected-(U3-P2_7-Pad3)") (class "Default")
      (node (ref "U3") (pin "3") (pinfunction "P2_7_3") (pintype "passive"))
    )
    (net (code "87") (name "unconnected-(U3-P3_3-Pad47)") (class "Default")
      (node (ref "U3") (pin "47") (pinfunction "P3_3_47") (pintype "passive"))
    )
    (net (code "88") (name "unconnected-(U3-P3_4-Pad48)") (class "Default")
      (node (ref "U3") (pin "48") (pinfunction "P3_4_48") (pintype "passive"))
    )
    (net (code "89") (name "unconnected-(U3-P3_5-Pad49)") (class "Default")
      (node (ref "U3") (pin "49") (pinfunction "P3_5_49") (pintype "passive"))
    )
    (net (code "90") (name "unconnected-(U3-P3_7-Pad52)") (class "Default")
      (node (ref "U3") (pin "52") (pinfunction "P3_7_52") (pintype "passive"))
    )
    (net (code "91") (name "unconnected-(U3-P4_2-Pad80)") (class "Default")
      (node (ref "U3") (pin "80") (pinfunction "P4_2_80") (pintype "passive"))
    )
    (net (code "92") (name "unconnected-(U3-P4_3-Pad81)") (class "Default")
      (node (ref "U3") (pin "81") (pinfunction "P4_3_81") (pintype "passive"))
    )
    (net (code "93") (name "unconnected-(U3-P4_4-Pad82)") (class "Default")
      (node (ref "U3") (pin "82") (pinfunction "P4_4_82") (pintype "passive"))
    )
    (net (code "94") (name "unconnected-(U3-P4_5-Pad83)") (class "Default")
      (node (ref "U3") (pin "83") (pinfunction "P4_5_83") (pintype "passive"))
    )
    (net (code "95") (name "unconnected-(U3-P4_7-Pad85)") (class "Default")
      (node (ref "U3") (pin "85") (pinfunction "P4_7_85") (pintype "passive"))
    )
    (net (code "96") (name "unconnected-(U3-P5_0-Pad16)") (class "Default")
      (node (ref "U3") (pin "16") (pinfunction "P5_0_16") (pintype "passive"))
    )
    (net (code "97") (name "unconnected-(U3-P5_1-Pad17)") (class "Default")
      (node (ref "U3") (pin "17") (pinfunction "P5_1_17") (pintype "passive"))
    )
    (net (code "98") (name "unconnected-(U3-P5_2-Pad18)") (class "Default")
      (node (ref "U3") (pin "18") (pinfunction "P5_2_18") (pintype "passive"))
    )
    (net (code "99") (name "unconnected-(U3-P5_3-Pad19)") (class "Default")
      (node (ref "U3") (pin "19") (pinfunction "P5_3_19") (pintype "passive"))
    )
    (net (code "100") (name "unconnected-(U3-P5_4-Pad31)") (class "Default")
      (node (ref "U3") (pin "31") (pinfunction "P5_4_31") (pintype "passive"))
    )
    (net (code "101") (name "unconnected-(U3-P5_5-Pad32)") (class "Default")
      (node (ref "U3") (pin "32") (pinfunction "P5_5_32") (pintype "passive"))
    )
    (net (code "102") (name "unconnected-(U3-P5_6-Pad33)") (class "Default")
      (node (ref "U3") (pin "33") (pinfunction "P5_6_33") (pintype "passive"))
    )
    (net (code "103") (name "unconnected-(U3-P5_7-Pad34)") (class "Default")
      (node (ref "U3") (pin "34") (pinfunction "P5_7_34") (pintype "passive"))
    )
    (net (code "104") (name "unconnected-(U3-P6_0-Pad89)") (class "Default")
      (node (ref "U3") (pin "89") (pinfunction "P6_0_89") (pintype "passive"))
    )
    (net (code "105") (name "unconnected-(U3-P6_1-Pad90)") (class "Default")
      (node (ref "U3") (pin "90") (pinfunction "P6_1_90") (pintype "passive"))
    )
    (net (code "106") (name "unconnected-(U3-P6_2-Pad91)") (class "Default")
      (node (ref "U3") (pin "91") (pinfunction "P6_2_91") (pintype "passive"))
    )
    (net (code "107") (name "unconnected-(U3-P6_3-Pad92)") (class "Default")
      (node (ref "U3") (pin "92") (pinfunction "P6_3_92") (pintype "passive"))
    )
    (net (code "108") (name "unconnected-(U3-P6_4-Pad6)") (class "Default")
      (node (ref "U3") (pin "6") (pinfunction "P6_4_6") (pintype "passive"))
    )
    (net (code "109") (name "unconnected-(U3-P6_5-Pad7)") (class "Default")
      (node (ref "U3") (pin "7") (pinfunction "P6_5_7") (pintype "passive"))
    )
    (net (code "110") (name "unconnected-(U3-P6_6-Pad8)") (class "Default")
      (node (ref "U3") (pin "8") (pinfunction "P6_6_8") (pintype "passive"))
    )
    (net (code "111") (name "unconnected-(U3-P6_7-Pad9)") (class "Default")
      (node (ref "U3") (pin "9") (pinfunction "P6_7_9") (pintype "passive"))
    )
    (net (code "112") (name "unconnected-(U3-P12_2-Pad67)") (class "Default")
      (node (ref "U3") (pin "67") (pinfunction "P12_2_67") (pintype "passive"))
    )
    (net (code "113") (name "unconnected-(U3-P12_3-Pad68)") (class "Default")
      (node (ref "U3") (pin "68") (pinfunction "P12_3_68") (pintype "passive"))
    )
    (net (code "114") (name "unconnected-(U3-P12_6-Pad29)") (class "Default")
      (node (ref "U3") (pin "29") (pinfunction "P12_6_29") (pintype "passive"))
    )
    (net (code "115") (name "unconnected-(U3-P12_7-Pad30)") (class "Default")
      (node (ref "U3") (pin "30") (pinfunction "P12_7_30") (pintype "passive"))
    )
    (net (code "116") (name "unconnected-(U3-P15_0_MXTLO-Pad42)") (class "Default")
      (node (ref "U3") (pin "42") (pinfunction "P15_0_MXTLO_42") (pintype "passive"))
    )
    (net (code "117") (name "unconnected-(U3-P15_1_MXTLI-Pad43)") (class "Default")
      (node (ref "U3") (pin "43") (pinfunction "P15_1_MXTLI_43") (pintype "passive"))
    )
    (net (code "118") (name "unconnected-(U3-P15_6_DP-Pad35)") (class "Default")
      (node (ref "U3") (pin "35") (pinfunction "P15_6_DP_35") (pintype "passive"))
    )
    (net (code "119") (name "unconnected-(U3-P15_7_DM-Pad36)") (class "Default")
      (node (ref "U3") (pin "36") (pinfunction "P15_7_DM_36") (pintype "passive"))
    )
    (net (code "120") (name "unconnected-(U3-VSSD-Pad66)") (class "Default")
      (node (ref "U3") (pin "66") (pinfunction "VSSD_66") (pintype "passive"))
    )
    (net (code "121") (name "unconnected-(U4-AD0{slash}DIO0-Pad20)") (class "Default")
      (node (ref "U4") (pin "20") (pinfunction "AD0/DIO0_20") (pintype "bidirectional"))
    )
    (net (code "122") (name "unconnected-(U4-AD1{slash}DIO1-Pad19)") (class "Default")
      (node (ref "U4") (pin "19") (pinfunction "AD1/DIO1_19") (pintype "bidirectional"))
    )
    (net (code "123") (name "unconnected-(U4-AD2{slash}DIO2-Pad18)") (class "Default")
      (node (ref "U4") (pin "18") (pinfunction "AD2/DIO2_18") (pintype "bidirectional"))
    )
    (net (code "124") (name "unconnected-(U4-AD3{slash}DIO3-Pad17)") (class "Default")
      (node (ref "U4") (pin "17") (pinfunction "AD3/DIO3_17") (pintype "bidirectional"))
    )
    (net (code "125") (name "unconnected-(U4-AD4{slash}DIO4-Pad11)") (class "Default")
      (node (ref "U4") (pin "11") (pinfunction "AD4/DIO4_11") (pintype "bidirectional"))
    )
    (net (code "126") (name "unconnected-(U4-ASC{slash}AD5{slash}DIO5-Pad15)") (class "Default")
      (node (ref "U4") (pin "15") (pinfunction "ASC/AD5/DIO5_15") (pintype "bidirectional"))
    )
    (net (code "127") (name "unconnected-(U4-CTS{slash}DIO7-Pad12)") (class "Default")
      (node (ref "U4") (pin "12") (pinfunction "CTS/DIO7_12") (pintype "bidirectional"))
    )
    (net (code "128") (name "unconnected-(U4-DO8-Pad4)") (class "Default")
      (node (ref "U4") (pin "4") (pinfunction "DO8_4") (pintype "output"))
    )
    (net (code "129") (name "unconnected-(U4-ON{slash}SLEEP-Pad13)") (class "Default")
      (node (ref "U4") (pin "13") (pinfunction "ON/SLEEP_13") (pintype "output"))
    )
    (net (code "130") (name "unconnected-(U4-PWM0{slash}RSSI-Pad6)") (class "Default")
      (node (ref "U4") (pin "6") (pinfunction "PWM0/RSSI_6") (pintype "output"))
    )
    (net (code "131") (name "unconnected-(U4-PWM1-Pad7)") (class "Default")
      (node (ref "U4") (pin "7") (pinfunction "PWM1_7") (pintype "output"))
    )
    (net (code "132") (name "unconnected-(U4-RESERVED-Pad8)") (class "Default")
      (node (ref "U4") (pin "8") (pinfunction "RESERVED_8") (pintype "no_connect"))
    )
    (net (code "133") (name "unconnected-(U4-RESET-Pad5)") (class "Default")
      (node (ref "U4") (pin "5") (pinfunction "RESET_5") (pintype "input"))
    )
    (net (code "134") (name "unconnected-(U4-RTS{slash}AD6{slash}DIO6-Pad16)") (class "Default")
      (node (ref "U4") (pin "16") (pinfunction "RTS/AD6/DIO6_16") (pintype "bidirectional"))
    )
    (net (code "135") (name "unconnected-(U4-VREF-Pad14)") (class "Default")
      (node (ref "U4") (pin "14") (pinfunction "VREF_14") (pintype "input"))
    )
    (net (code "136") (name "unconnected-(U6-A6-PadP$23)") (class "Default")
      (node (ref "U6") (pin "P$23") (pinfunction "A6_P$23") (pintype "bidirectional"))
    )
    (net (code "137") (name "unconnected-(U6-A7-PadP$20)") (class "Default")
      (node (ref "U6") (pin "P$20") (pinfunction "A7_P$20") (pintype "bidirectional"))
    )
    (net (code "138") (name "unconnected-(U6-B6-PadP$26)") (class "Default")
      (node (ref "U6") (pin "P$26") (pinfunction "B6_P$26") (pintype "bidirectional"))
    )
    (net (code "139") (name "unconnected-(U6-B7-PadP$29)") (class "Default")
      (node (ref "U6") (pin "P$29") (pinfunction "B7_P$29") (pintype "bidirectional"))
    )
    (net (code "140") (name "unconnected-(U6-C6-PadP$39)") (class "Default")
      (node (ref "U6") (pin "P$39") (pinfunction "C6_P$39") (pintype "bidirectional"))
    )
    (net (code "141") (name "unconnected-(U6-C7-PadP$36)") (class "Default")
      (node (ref "U6") (pin "P$36") (pinfunction "C7_P$36") (pintype "bidirectional"))
    )
    (net (code "142") (name "unconnected-(U6-D6-PadP$42)") (class "Default")
      (node (ref "U6") (pin "P$42") (pinfunction "D6_P$42") (pintype "bidirectional"))
    )
    (net (code "143") (name "unconnected-(U6-D7-PadP$45)") (class "Default")
      (node (ref "U6") (pin "P$45") (pinfunction "D7_P$45") (pintype "bidirectional"))
    )
  )
)
